# ADC_DSP.net
KiCad netlist of a schematic drawn in EAGLE
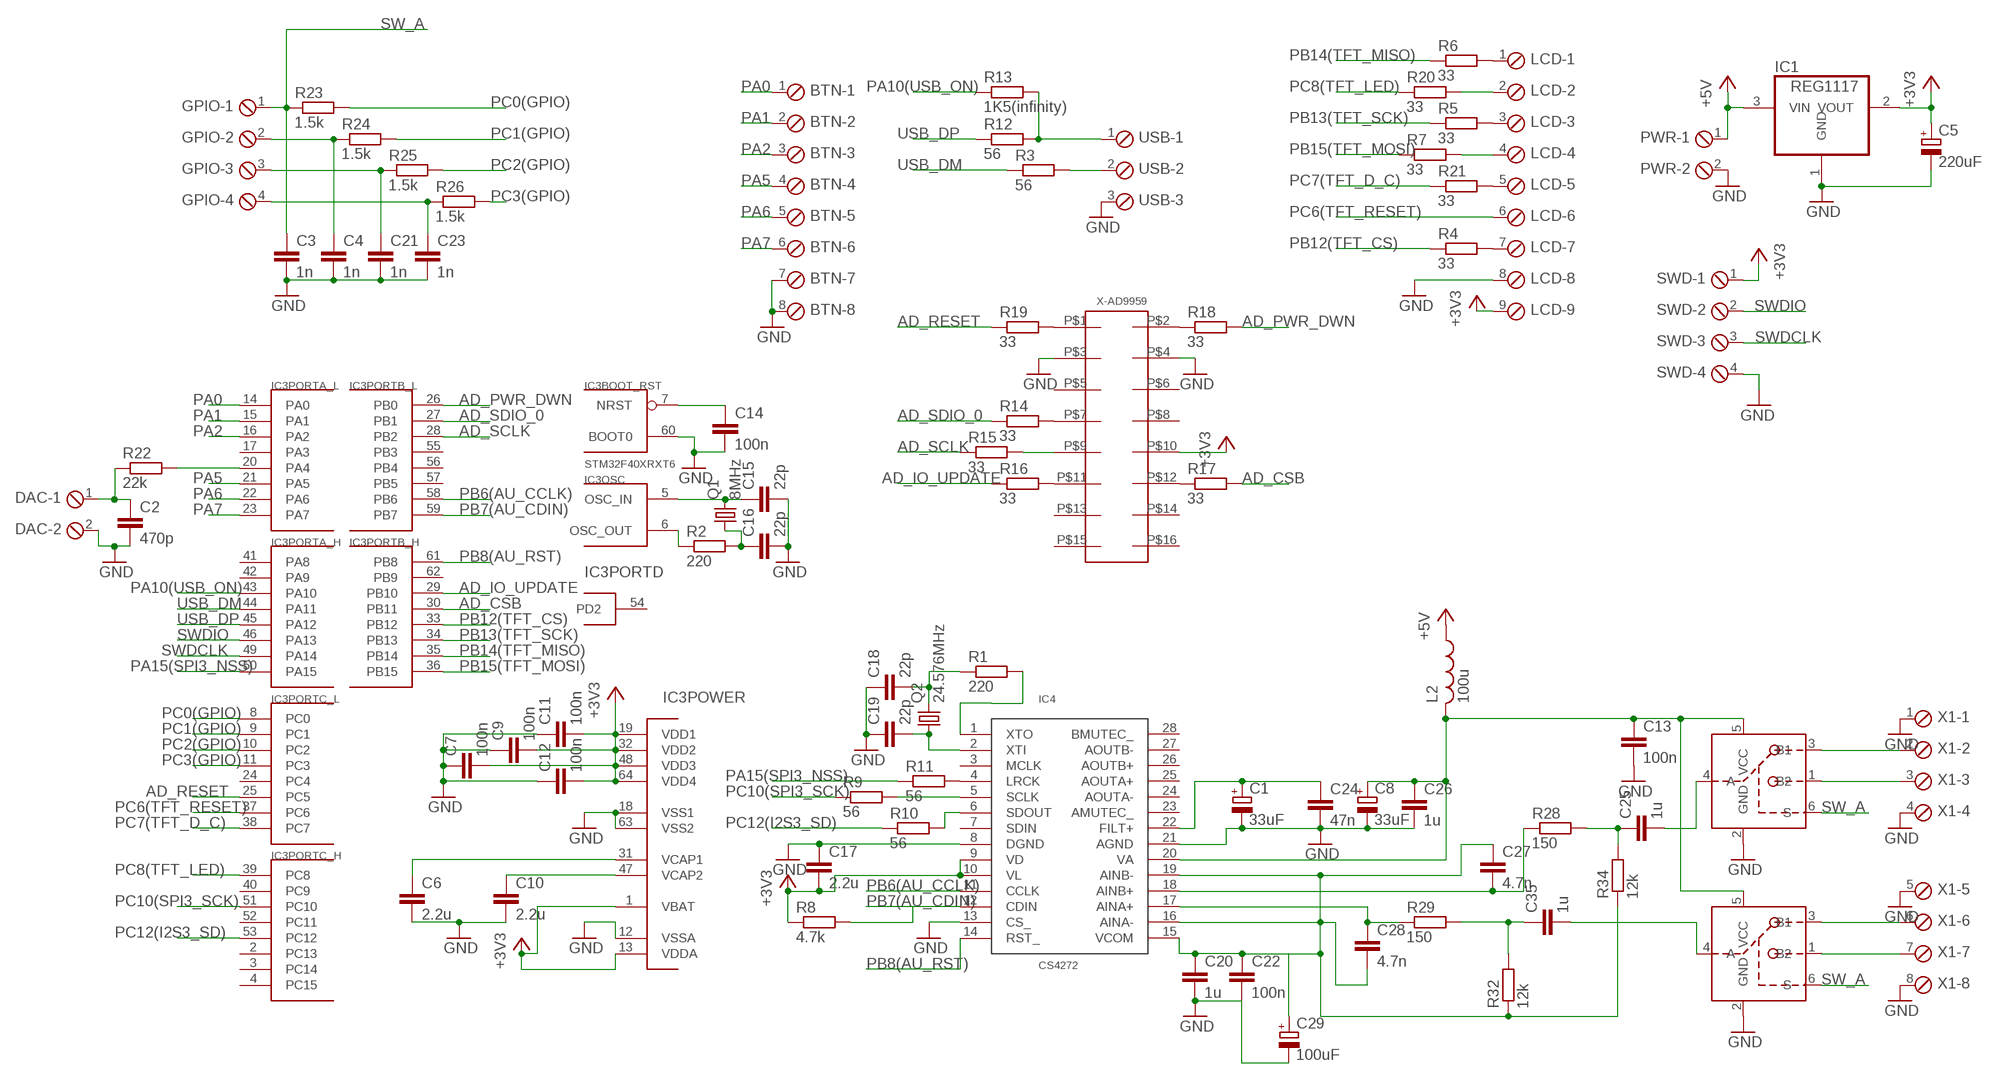
[diagram p0: schematic, sheet 1]

(export (version "E")
  (design (tool "Eeschema 10.0.6"))
  (components
    (comp (ref "BTN")
      (value "MPT8")
      (footprint "eagle-import:8POL254")
      (libsource (lib "eagle-import") (part "MPT8"))
    )
    (comp (ref "C1")
      (value "33uF")
      (footprint "eagle-import:153CLV-0605")
      (libsource (lib "eagle-import") (part "CPOL-EU153CLV-0605"))
    )
    (comp (ref "C2")
      (value "470p")
      (footprint "eagle-import:C0805")
      (libsource (lib "eagle-import") (part "C-EUC0805"))
    )
    (comp (ref "C3")
      (value "1n")
      (footprint "eagle-import:C0805")
      (libsource (lib "eagle-import") (part "C-EUC0805"))
    )
    (comp (ref "C4")
      (value "1n")
      (footprint "eagle-import:C0805")
      (libsource (lib "eagle-import") (part "C-EUC0805"))
    )
    (comp (ref "C5")
      (value "220uF")
      (footprint "eagle-import:153CLV-0605")
      (libsource (lib "eagle-import") (part "CPOL-EU153CLV-0605"))
    )
    (comp (ref "C6")
      (value "2.2u")
      (footprint "eagle-import:C0603")
      (libsource (lib "eagle-import") (part "C-EUC0603"))
    )
    (comp (ref "C7")
      (value "100n")
      (footprint "eagle-import:C0603")
      (libsource (lib "eagle-import") (part "C-EUC0603"))
    )
    (comp (ref "C8")
      (value "33uF")
      (footprint "eagle-import:153CLV-0605")
      (libsource (lib "eagle-import") (part "CPOL-EU153CLV-0605"))
    )
    (comp (ref "C9")
      (value "100n")
      (footprint "eagle-import:C0603")
      (libsource (lib "eagle-import") (part "C-EUC0603"))
    )
    (comp (ref "C10")
      (value "2.2u")
      (footprint "eagle-import:C0603")
      (libsource (lib "eagle-import") (part "C-EUC0603"))
    )
    (comp (ref "C11")
      (value "100n")
      (footprint "eagle-import:C0603")
      (libsource (lib "eagle-import") (part "C-EUC0603"))
    )
    (comp (ref "C12")
      (value "100n")
      (footprint "eagle-import:C0603")
      (libsource (lib "eagle-import") (part "C-EUC0603"))
    )
    (comp (ref "C13")
      (value "100n")
      (footprint "eagle-import:C0603")
      (libsource (lib "eagle-import") (part "C-EUC0603"))
    )
    (comp (ref "C14")
      (value "100n")
      (footprint "eagle-import:C0603")
      (libsource (lib "eagle-import") (part "C-EUC0603"))
    )
    (comp (ref "C15")
      (value "22p")
      (footprint "eagle-import:C0603")
      (libsource (lib "eagle-import") (part "C-EUC0603"))
    )
    (comp (ref "C16")
      (value "22p")
      (footprint "eagle-import:C0603")
      (libsource (lib "eagle-import") (part "C-EUC0603"))
    )
    (comp (ref "C17")
      (value "2.2u")
      (footprint "eagle-import:C0603")
      (libsource (lib "eagle-import") (part "C-EUC0603"))
    )
    (comp (ref "C18")
      (value "22p")
      (footprint "eagle-import:C0603")
      (libsource (lib "eagle-import") (part "C-EUC0603"))
    )
    (comp (ref "C19")
      (value "22p")
      (footprint "eagle-import:C0603")
      (libsource (lib "eagle-import") (part "C-EUC0603"))
    )
    (comp (ref "C20")
      (value "1u")
      (footprint "eagle-import:C0603")
      (libsource (lib "eagle-import") (part "C-EUC0603"))
    )
    (comp (ref "C21")
      (value "1n")
      (footprint "eagle-import:C0805")
      (libsource (lib "eagle-import") (part "C-EUC0805"))
    )
    (comp (ref "C22")
      (value "100n")
      (footprint "eagle-import:C0603")
      (libsource (lib "eagle-import") (part "C-EUC0603"))
    )
    (comp (ref "C23")
      (value "1n")
      (footprint "eagle-import:C0805")
      (libsource (lib "eagle-import") (part "C-EUC0805"))
    )
    (comp (ref "C24")
      (value "47n")
      (footprint "eagle-import:C0805")
      (libsource (lib "eagle-import") (part "C-EUC0805"))
    )
    (comp (ref "C25")
      (value "1u")
      (footprint "eagle-import:C0603")
      (libsource (lib "eagle-import") (part "C-EUC0603"))
    )
    (comp (ref "C26")
      (value "1u")
      (footprint "eagle-import:C0603")
      (libsource (lib "eagle-import") (part "C-EUC0603"))
    )
    (comp (ref "C27")
      (value "4.7n")
      (footprint "eagle-import:C0805")
      (libsource (lib "eagle-import") (part "C-EUC0805"))
    )
    (comp (ref "C28")
      (value "4.7n")
      (footprint "eagle-import:C0805")
      (libsource (lib "eagle-import") (part "C-EUC0805"))
    )
    (comp (ref "C29")
      (value "100uF")
      (footprint "eagle-import:153CLV-0605")
      (libsource (lib "eagle-import") (part "CPOL-EU153CLV-0605"))
    )
    (comp (ref "C35")
      (value "1u")
      (footprint "eagle-import:C0603")
      (libsource (lib "eagle-import") (part "C-EUC0603"))
    )
    (comp (ref "DAC")
      (value "MPT2")
      (footprint "eagle-import:2POL254")
      (libsource (lib "eagle-import") (part "MPT2"))
    )
    (comp (ref "GPIO")
      (value "MPT4")
      (footprint "eagle-import:4POL254")
      (libsource (lib "eagle-import") (part "MPT4"))
    )
    (comp (ref "IC1")
      (value "REG1117")
      (footprint "eagle-import:SOT223")
      (libsource (lib "eagle-import") (part "REG1117"))
    )
    (comp (ref "IC3")
      (value "STM32F40XRXT6")
      (footprint "eagle-import:TQFP64")
      (libsource (lib "eagle-import") (part "STM32F40XRXT6"))
    )
    (comp (ref "IC4")
      (value "CS4272")
      (footprint "eagle-import:TSSOP28")
      (libsource (lib "eagle-import") (part "CS4272"))
    )
    (comp (ref "L2")
      (value "100u")
      (footprint "eagle-import:0207_12")
      (libsource (lib "eagle-import") (part "L-US0207/12"))
    )
    (comp (ref "LCD")
      (value "MPT9")
      (footprint "eagle-import:9POL254")
      (libsource (lib "eagle-import") (part "MPT9"))
    )
    (comp (ref "PWR")
      (value "MPT2")
      (footprint "eagle-import:2POL254")
      (libsource (lib "eagle-import") (part "MPT2"))
    )
    (comp (ref "Q1")
      (value "8MHz")
      (footprint "eagle-import:HC49_S")
      (libsource (lib "eagle-import") (part "CRYSTALHC49S"))
    )
    (comp (ref "Q2")
      (value "24.576MHz")
      (footprint "eagle-import:HC49_S")
      (libsource (lib "eagle-import") (part "CRYSTALHC49S"))
    )
    (comp (ref "R1")
      (value "220")
      (footprint "eagle-import:R0603")
      (libsource (lib "eagle-import") (part "R-EU_R0603"))
    )
    (comp (ref "R2")
      (value "220")
      (footprint "eagle-import:R0603")
      (libsource (lib "eagle-import") (part "R-EU_R0603"))
    )
    (comp (ref "R3")
      (value "56")
      (footprint "eagle-import:R0603")
      (libsource (lib "eagle-import") (part "R-EU_R0603"))
    )
    (comp (ref "R4")
      (value "33")
      (footprint "eagle-import:R0603")
      (libsource (lib "eagle-import") (part "R-EU_R0603"))
    )
    (comp (ref "R5")
      (value "33")
      (footprint "eagle-import:R0603")
      (libsource (lib "eagle-import") (part "R-EU_R0603"))
    )
    (comp (ref "R6")
      (value "33")
      (footprint "eagle-import:R0603")
      (libsource (lib "eagle-import") (part "R-EU_R0603"))
    )
    (comp (ref "R7")
      (value "33")
      (footprint "eagle-import:R0603")
      (libsource (lib "eagle-import") (part "R-EU_R0603"))
    )
    (comp (ref "R8")
      (value "4.7k")
      (footprint "eagle-import:R0603")
      (libsource (lib "eagle-import") (part "R-EU_R0603"))
    )
    (comp (ref "R9")
      (value "56")
      (footprint "eagle-import:R0603")
      (libsource (lib "eagle-import") (part "R-EU_R0603"))
    )
    (comp (ref "R10")
      (value "56")
      (footprint "eagle-import:R0603")
      (libsource (lib "eagle-import") (part "R-EU_R0603"))
    )
    (comp (ref "R11")
      (value "56")
      (footprint "eagle-import:R0603")
      (libsource (lib "eagle-import") (part "R-EU_R0603"))
    )
    (comp (ref "R12")
      (value "56")
      (footprint "eagle-import:R0603")
      (libsource (lib "eagle-import") (part "R-EU_R0603"))
    )
    (comp (ref "R13")
      (value "1K5(infinity)")
      (footprint "eagle-import:R0603")
      (libsource (lib "eagle-import") (part "R-EU_R0603"))
    )
    (comp (ref "R14")
      (value "33")
      (footprint "eagle-import:R0603")
      (libsource (lib "eagle-import") (part "R-EU_R0603"))
    )
    (comp (ref "R15")
      (value "33")
      (footprint "eagle-import:R0603")
      (libsource (lib "eagle-import") (part "R-EU_R0603"))
    )
    (comp (ref "R16")
      (value "33")
      (footprint "eagle-import:R0603")
      (libsource (lib "eagle-import") (part "R-EU_R0603"))
    )
    (comp (ref "R17")
      (value "33")
      (footprint "eagle-import:R0603")
      (libsource (lib "eagle-import") (part "R-EU_R0603"))
    )
    (comp (ref "R18")
      (value "33")
      (footprint "eagle-import:R0603")
      (libsource (lib "eagle-import") (part "R-EU_R0603"))
    )
    (comp (ref "R19")
      (value "33")
      (footprint "eagle-import:R0603")
      (libsource (lib "eagle-import") (part "R-EU_R0603"))
    )
    (comp (ref "R20")
      (value "33")
      (footprint "eagle-import:R0603")
      (libsource (lib "eagle-import") (part "R-EU_R0603"))
    )
    (comp (ref "R21")
      (value "33")
      (footprint "eagle-import:R0603")
      (libsource (lib "eagle-import") (part "R-EU_R0603"))
    )
    (comp (ref "R22")
      (value "22k")
      (footprint "eagle-import:R0603")
      (libsource (lib "eagle-import") (part "R-EU_R0603"))
    )
    (comp (ref "R23")
      (value "1.5k")
      (footprint "eagle-import:R0603")
      (libsource (lib "eagle-import") (part "R-EU_R0603"))
    )
    (comp (ref "R24")
      (value "1.5k")
      (footprint "eagle-import:R0603")
      (libsource (lib "eagle-import") (part "R-EU_R0603"))
    )
    (comp (ref "R25")
      (value "1.5k")
      (footprint "eagle-import:R0603")
      (libsource (lib "eagle-import") (part "R-EU_R0603"))
    )
    (comp (ref "R26")
      (value "1.5k")
      (footprint "eagle-import:R0603")
      (libsource (lib "eagle-import") (part "R-EU_R0603"))
    )
    (comp (ref "R28")
      (value "150")
      (footprint "eagle-import:R0603")
      (libsource (lib "eagle-import") (part "R-EU_R0603"))
    )
    (comp (ref "R29")
      (value "150")
      (footprint "eagle-import:R0603")
      (libsource (lib "eagle-import") (part "R-EU_R0603"))
    )
    (comp (ref "R32")
      (value "12k")
      (footprint "eagle-import:R0603")
      (libsource (lib "eagle-import") (part "R-EU_R0603"))
    )
    (comp (ref "R34")
      (value "12k")
      (footprint "eagle-import:R0603")
      (libsource (lib "eagle-import") (part "R-EU_R0603"))
    )
    (comp (ref "SWD")
      (value "MPT4")
      (footprint "eagle-import:4POL254")
      (libsource (lib "eagle-import") (part "MPT4"))
    )
    (comp (ref "U$1")
      (value "SN74LVC1G3157DBVR")
      (footprint "eagle-import:SOT23-6")
      (libsource (lib "eagle-import") (part "SN74LVC1G3157DBVR"))
    )
    (comp (ref "U$2")
      (value "SN74LVC1G3157DBVR")
      (footprint "eagle-import:SOT23-6")
      (libsource (lib "eagle-import") (part "SN74LVC1G3157DBVR"))
    )
    (comp (ref "USB")
      (value "MPT3")
      (footprint "eagle-import:3POL254")
      (libsource (lib "eagle-import") (part "MPT3"))
    )
    (comp (ref "X-AD9959")
      (value "PIN8X2")
      (footprint "eagle-import:PIN8X2_SMD")
      (libsource (lib "eagle-import") (part "PIN8X2"))
    )
    (comp (ref "X1")
      (value "MPT8")
      (footprint "eagle-import:8POL254")
      (libsource (lib "eagle-import") (part "MPT8"))
    )
  )
  (nets
    (net (code "1") (name "+3V3") (class "Default")
      (node (ref "C11") (pin "2") (pinfunction "2_2") (pintype "passive"))
      (node (ref "C12") (pin "2") (pinfunction "2_2") (pintype "passive"))
      (node (ref "C17") (pin "2") (pinfunction "2_2") (pintype "passive"))
      (node (ref "C5") (pin "+") (pinfunction "+_+") (pintype "passive"))
      (node (ref "C7") (pin "2") (pinfunction "2_2") (pintype "passive"))
      (node (ref "C9") (pin "2") (pinfunction "2_2") (pintype "passive"))
      (node (ref "IC1") (pin "2") (pinfunction "VOUT_2") (pintype "output"))
      (node (ref "IC3") (pin "1") (pinfunction "VBAT_1") (pintype "bidirectional"))
      (node (ref "IC3") (pin "13") (pinfunction "VDDA_13") (pintype "bidirectional"))
      (node (ref "IC3") (pin "19") (pinfunction "VDD1_19") (pintype "bidirectional"))
      (node (ref "IC3") (pin "32") (pinfunction "VDD2_32") (pintype "bidirectional"))
      (node (ref "IC3") (pin "48") (pinfunction "VDD3_48") (pintype "bidirectional"))
      (node (ref "IC3") (pin "64") (pinfunction "VDD4_64") (pintype "bidirectional"))
      (node (ref "IC4") (pin "10") (pinfunction "VL_10") (pintype "bidirectional"))
      (node (ref "IC4") (pin "9") (pinfunction "VD_9") (pintype "bidirectional"))
      (node (ref "LCD") (pin "9") (pinfunction "1_9") (pintype "passive"))
      (node (ref "R8") (pin "1") (pinfunction "1_1") (pintype "passive"))
      (node (ref "SWD") (pin "1") (pinfunction "1_1") (pintype "passive"))
      (node (ref "X-AD9959") (pin "P$10") (pinfunction "P$10_P$10") (pintype "bidirectional"))
    )
    (net (code "2") (name "+5V") (class "Default")
      (node (ref "IC1") (pin "3") (pinfunction "VIN_3") (pintype "input"))
      (node (ref "L2") (pin "1") (pinfunction "1_1") (pintype "passive"))
      (node (ref "PWR") (pin "1") (pinfunction "1_1") (pintype "passive"))
    )
    (net (code "3") (name "/AD_CSB") (class "Default")
      (node (ref "IC3") (pin "30") (pinfunction "PB11_30") (pintype "bidirectional"))
      (node (ref "R17") (pin "2") (pinfunction "2_2") (pintype "passive"))
    )
    (net (code "4") (name "/AD_IO_UPDATE") (class "Default")
      (node (ref "IC3") (pin "29") (pinfunction "PB10_29") (pintype "bidirectional"))
      (node (ref "R16") (pin "1") (pinfunction "1_1") (pintype "passive"))
    )
    (net (code "5") (name "/AD_PWR_DWN") (class "Default")
      (node (ref "IC3") (pin "26") (pinfunction "PB0_26") (pintype "bidirectional"))
      (node (ref "R18") (pin "2") (pinfunction "2_2") (pintype "passive"))
    )
    (net (code "6") (name "/AD_RESET") (class "Default")
      (node (ref "IC3") (pin "25") (pinfunction "PC5_25") (pintype "bidirectional"))
      (node (ref "R19") (pin "1") (pinfunction "1_1") (pintype "passive"))
    )
    (net (code "7") (name "/AD_SCLK") (class "Default")
      (node (ref "IC3") (pin "28") (pinfunction "PB2_28") (pintype "bidirectional"))
      (node (ref "R15") (pin "1") (pinfunction "1_1") (pintype "passive"))
    )
    (net (code "8") (name "/AD_SDIO_0") (class "Default")
      (node (ref "IC3") (pin "27") (pinfunction "PB1_27") (pintype "bidirectional"))
      (node (ref "R14") (pin "1") (pinfunction "1_1") (pintype "passive"))
    )
    (net (code "9") (name "/PA0") (class "Default")
      (node (ref "BTN") (pin "1") (pinfunction "1_1") (pintype "passive"))
      (node (ref "IC3") (pin "14") (pinfunction "PA0_14") (pintype "bidirectional"))
    )
    (net (code "10") (name "/PA1") (class "Default")
      (node (ref "BTN") (pin "2") (pinfunction "1_2") (pintype "passive"))
      (node (ref "IC3") (pin "15") (pinfunction "PA1_15") (pintype "bidirectional"))
    )
    (net (code "11") (name "/PA2") (class "Default")
      (node (ref "BTN") (pin "3") (pinfunction "1_3") (pintype "passive"))
      (node (ref "IC3") (pin "16") (pinfunction "PA2_16") (pintype "bidirectional"))
    )
    (net (code "12") (name "/PA5") (class "Default")
      (node (ref "BTN") (pin "4") (pinfunction "1_4") (pintype "passive"))
      (node (ref "IC3") (pin "21") (pinfunction "PA5_21") (pintype "bidirectional"))
    )
    (net (code "13") (name "/PA6") (class "Default")
      (node (ref "BTN") (pin "5") (pinfunction "1_5") (pintype "passive"))
      (node (ref "IC3") (pin "22") (pinfunction "PA6_22") (pintype "bidirectional"))
    )
    (net (code "14") (name "/PA7") (class "Default")
      (node (ref "BTN") (pin "6") (pinfunction "1_6") (pintype "passive"))
      (node (ref "IC3") (pin "23") (pinfunction "PA7_23") (pintype "bidirectional"))
    )
    (net (code "15") (name "/PA10(USB_ON)") (class "Default")
      (node (ref "IC3") (pin "43") (pinfunction "PA10_43") (pintype "bidirectional"))
      (node (ref "R13") (pin "1") (pinfunction "1_1") (pintype "passive"))
    )
    (net (code "16") (name "/PA15(SPI3_NSS)") (class "Default")
      (node (ref "IC3") (pin "50") (pinfunction "PA15_50") (pintype "bidirectional"))
      (node (ref "R11") (pin "1") (pinfunction "1_1") (pintype "passive"))
    )
    (net (code "17") (name "/PB6(AU_CCLK)") (class "Default")
      (node (ref "IC3") (pin "58") (pinfunction "PB6_58") (pintype "bidirectional"))
      (node (ref "IC4") (pin "11") (pinfunction "CCLK_11") (pintype "bidirectional"))
    )
    (net (code "18") (name "/PB7(AU_CDIN)") (class "Default")
      (node (ref "IC3") (pin "59") (pinfunction "PB7_59") (pintype "bidirectional"))
      (node (ref "IC4") (pin "12") (pinfunction "CDIN_12") (pintype "bidirectional"))
      (node (ref "R8") (pin "2") (pinfunction "2_2") (pintype "passive"))
    )
    (net (code "19") (name "/PB8(AU_RST)") (class "Default")
      (node (ref "IC3") (pin "61") (pinfunction "PB8_61") (pintype "bidirectional"))
      (node (ref "IC4") (pin "14") (pinfunction "RST__14") (pintype "bidirectional"))
    )
    (net (code "20") (name "/PB12(TFT_CS)") (class "Default")
      (node (ref "IC3") (pin "33") (pinfunction "PB12_33") (pintype "bidirectional"))
      (node (ref "R4") (pin "1") (pinfunction "1_1") (pintype "passive"))
    )
    (net (code "21") (name "/PB13(TFT_SCK)") (class "Default")
      (node (ref "IC3") (pin "34") (pinfunction "PB13_34") (pintype "bidirectional"))
      (node (ref "R5") (pin "1") (pinfunction "1_1") (pintype "passive"))
    )
    (net (code "22") (name "/PB14(TFT_MISO)") (class "Default")
      (node (ref "IC3") (pin "35") (pinfunction "PB14_35") (pintype "bidirectional"))
      (node (ref "R6") (pin "1") (pinfunction "1_1") (pintype "passive"))
    )
    (net (code "23") (name "/PB15(TFT_MOSI)") (class "Default")
      (node (ref "IC3") (pin "36") (pinfunction "PB15_36") (pintype "bidirectional"))
      (node (ref "R7") (pin "1") (pinfunction "1_1") (pintype "passive"))
    )
    (net (code "24") (name "/PC0(GPIO)") (class "Default")
      (node (ref "IC3") (pin "8") (pinfunction "PC0_8") (pintype "bidirectional"))
      (node (ref "R23") (pin "2") (pinfunction "2_2") (pintype "passive"))
    )
    (net (code "25") (name "/PC1(GPIO)") (class "Default")
      (node (ref "IC3") (pin "9") (pinfunction "PC1_9") (pintype "bidirectional"))
      (node (ref "R24") (pin "2") (pinfunction "2_2") (pintype "passive"))
    )
    (net (code "26") (name "/PC2(GPIO)") (class "Default")
      (node (ref "IC3") (pin "10") (pinfunction "PC2_10") (pintype "bidirectional"))
      (node (ref "R25") (pin "2") (pinfunction "2_2") (pintype "passive"))
    )
    (net (code "27") (name "/PC3(GPIO)") (class "Default")
      (node (ref "IC3") (pin "11") (pinfunction "PC3_11") (pintype "bidirectional"))
      (node (ref "R26") (pin "2") (pinfunction "2_2") (pintype "passive"))
    )
    (net (code "28") (name "/PC6(TFT_RESET)") (class "Default")
      (node (ref "IC3") (pin "37") (pinfunction "PC6_37") (pintype "bidirectional"))
      (node (ref "LCD") (pin "6") (pinfunction "1_6") (pintype "passive"))
    )
    (net (code "29") (name "/PC7(TFT_D_C)") (class "Default")
      (node (ref "IC3") (pin "38") (pinfunction "PC7_38") (pintype "bidirectional"))
      (node (ref "R21") (pin "1") (pinfunction "1_1") (pintype "passive"))
    )
    (net (code "30") (name "/PC8(TFT_LED)") (class "Default")
      (node (ref "IC3") (pin "39") (pinfunction "PC8_39") (pintype "bidirectional"))
      (node (ref "R20") (pin "1") (pinfunction "1_1") (pintype "passive"))
    )
    (net (code "31") (name "/PC10(SPI3_SCK)") (class "Default")
      (node (ref "IC3") (pin "51") (pinfunction "PC10_51") (pintype "bidirectional"))
      (node (ref "R9") (pin "1") (pinfunction "1_1") (pintype "passive"))
    )
    (net (code "32") (name "/PC12(I2S3_SD)") (class "Default")
      (node (ref "IC3") (pin "53") (pinfunction "PC12_53") (pintype "bidirectional"))
      (node (ref "R10") (pin "1") (pinfunction "1_1") (pintype "passive"))
    )
    (net (code "33") (name "/SWDCLK") (class "Default")
      (node (ref "IC3") (pin "49") (pinfunction "PA14_49") (pintype "bidirectional"))
      (node (ref "SWD") (pin "3") (pinfunction "1_3") (pintype "passive"))
    )
    (net (code "34") (name "/SWDIO") (class "Default")
      (node (ref "IC3") (pin "46") (pinfunction "PA13_46") (pintype "bidirectional"))
      (node (ref "SWD") (pin "2") (pinfunction "1_2") (pintype "passive"))
    )
    (net (code "35") (name "/SW_A") (class "Default")
      (node (ref "C3") (pin "1") (pinfunction "1_1") (pintype "passive"))
      (node (ref "GPIO") (pin "1") (pinfunction "1_1") (pintype "passive"))
      (node (ref "R23") (pin "1") (pinfunction "1_1") (pintype "passive"))
      (node (ref "U$1") (pin "6") (pinfunction "S_6") (pintype "bidirectional"))
      (node (ref "U$2") (pin "6") (pinfunction "S_6") (pintype "bidirectional"))
    )
    (net (code "36") (name "/USB_DM") (class "Default")
      (node (ref "IC3") (pin "44") (pinfunction "PA11_44") (pintype "bidirectional"))
      (node (ref "R3") (pin "1") (pinfunction "1_1") (pintype "passive"))
    )
    (net (code "37") (name "/USB_DP") (class "Default")
      (node (ref "IC3") (pin "45") (pinfunction "PA12_45") (pintype "bidirectional"))
      (node (ref "R12") (pin "1") (pinfunction "1_1") (pintype "passive"))
    )
    (net (code "38") (name "GND") (class "Default")
      (node (ref "BTN") (pin "7") (pinfunction "1_7") (pintype "passive"))
      (node (ref "BTN") (pin "8") (pinfunction "1_8") (pintype "passive"))
      (node (ref "C1") (pin "-") (pinfunction "-_-") (pintype "passive"))
      (node (ref "C10") (pin "2") (pinfunction "2_2") (pintype "passive"))
      (node (ref "C11") (pin "1") (pinfunction "1_1") (pintype "passive"))
      (node (ref "C12") (pin "1") (pinfunction "1_1") (pintype "passive"))
      (node (ref "C13") (pin "2") (pinfunction "2_2") (pintype "passive"))
      (node (ref "C14") (pin "2") (pinfunction "2_2") (pintype "passive"))
      (node (ref "C15") (pin "2") (pinfunction "2_2") (pintype "passive"))
      (node (ref "C16") (pin "2") (pinfunction "2_2") (pintype "passive"))
      (node (ref "C17") (pin "1") (pinfunction "1_1") (pintype "passive"))
      (node (ref "C18") (pin "1") (pinfunction "1_1") (pintype "passive"))
      (node (ref "C19") (pin "1") (pinfunction "1_1") (pintype "passive"))
      (node (ref "C2") (pin "2") (pinfunction "2_2") (pintype "passive"))
      (node (ref "C20") (pin "2") (pinfunction "2_2") (pintype "passive"))
      (node (ref "C21") (pin "2") (pinfunction "2_2") (pintype "passive"))
      (node (ref "C22") (pin "2") (pinfunction "2_2") (pintype "passive"))
      (node (ref "C23") (pin "2") (pinfunction "2_2") (pintype "passive"))
      (node (ref "C24") (pin "2") (pinfunction "2_2") (pintype "passive"))
      (node (ref "C26") (pin "2") (pinfunction "2_2") (pintype "passive"))
      (node (ref "C29") (pin "-") (pinfunction "-_-") (pintype "passive"))
      (node (ref "C3") (pin "2") (pinfunction "2_2") (pintype "passive"))
      (node (ref "C4") (pin "2") (pinfunction "2_2") (pintype "passive"))
      (node (ref "C5") (pin "-") (pinfunction "-_-") (pintype "passive"))
      (node (ref "C6") (pin "2") (pinfunction "2_2") (pintype "passive"))
      (node (ref "C7") (pin "1") (pinfunction "1_1") (pintype "passive"))
      (node (ref "C8") (pin "-") (pinfunction "-_-") (pintype "passive"))
      (node (ref "C9") (pin "1") (pinfunction "1_1") (pintype "passive"))
      (node (ref "DAC") (pin "2") (pinfunction "1_2") (pintype "passive"))
      (node (ref "IC1") (pin "1") (pinfunction "GND_1") (pintype "power_in"))
      (node (ref "IC3") (pin "12") (pinfunction "VSSA_12") (pintype "bidirectional"))
      (node (ref "IC3") (pin "18") (pinfunction "VSS1_18") (pintype "bidirectional"))
      (node (ref "IC3") (pin "60") (pinfunction "BOOT0_60") (pintype "input"))
      (node (ref "IC3") (pin "63") (pinfunction "VSS2_63") (pintype "bidirectional"))
      (node (ref "IC4") (pin "13") (pinfunction "CS__13") (pintype "bidirectional"))
      (node (ref "IC4") (pin "21") (pinfunction "AGND_21") (pintype "bidirectional"))
      (node (ref "IC4") (pin "8") (pinfunction "DGND_8") (pintype "bidirectional"))
      (node (ref "LCD") (pin "8") (pinfunction "1_8") (pintype "passive"))
      (node (ref "PWR") (pin "2") (pinfunction "1_2") (pintype "passive"))
      (node (ref "SWD") (pin "4") (pinfunction "1_4") (pintype "passive"))
      (node (ref "U$1") (pin "2") (pinfunction "GND_2") (pintype "power_in"))
      (node (ref "U$2") (pin "2") (pinfunction "GND_2") (pintype "power_in"))
      (node (ref "USB") (pin "3") (pinfunction "1_3") (pintype "passive"))
      (node (ref "X-AD9959") (pin "P$3") (pinfunction "P$3_P$3") (pintype "bidirectional"))
      (node (ref "X-AD9959") (pin "P$4") (pinfunction "P$4_P$4") (pintype "bidirectional"))
      (node (ref "X1") (pin "1") (pinfunction "1_1") (pintype "passive"))
      (node (ref "X1") (pin "4") (pinfunction "1_4") (pintype "passive"))
      (node (ref "X1") (pin "5") (pinfunction "1_5") (pintype "passive"))
      (node (ref "X1") (pin "8") (pinfunction "1_8") (pintype "passive"))
    )
    (net (code "39") (name "Net-(C2-Pad1)") (class "Default")
      (node (ref "C2") (pin "1") (pinfunction "1_1") (pintype "passive"))
      (node (ref "DAC") (pin "1") (pinfunction "1_1") (pintype "passive"))
      (node (ref "R22") (pin "1") (pinfunction "1_1") (pintype "passive"))
    )
    (net (code "40") (name "Net-(C16-Pad1)") (class "Default")
      (node (ref "C16") (pin "1") (pinfunction "1_1") (pintype "passive"))
      (node (ref "Q1") (pin "1") (pinfunction "1_1") (pintype "passive"))
      (node (ref "R2") (pin "2") (pinfunction "2_2") (pintype "passive"))
    )
    (net (code "41") (name "Net-(C18-Pad2)") (class "Default")
      (node (ref "C18") (pin "2") (pinfunction "2_2") (pintype "passive"))
      (node (ref "Q2") (pin "2") (pinfunction "2_2") (pintype "passive"))
      (node (ref "R1") (pin "1") (pinfunction "1_1") (pintype "passive"))
    )
    (net (code "42") (name "Net-(C25-Pad1)") (class "Default")
      (node (ref "C25") (pin "1") (pinfunction "1_1") (pintype "passive"))
      (node (ref "R28") (pin "2") (pinfunction "2_2") (pintype "passive"))
      (node (ref "R34") (pin "2") (pinfunction "2_2") (pintype "passive"))
    )
    (net (code "43") (name "Net-(C35-Pad1)") (class "Default")
      (node (ref "C35") (pin "1") (pinfunction "1_1") (pintype "passive"))
      (node (ref "R29") (pin "2") (pinfunction "2_2") (pintype "passive"))
      (node (ref "R32") (pin "2") (pinfunction "2_2") (pintype "passive"))
    )
    (net (code "44") (name "Net-(GPIOB-1)") (class "Default")
      (node (ref "C4") (pin "1") (pinfunction "1_1") (pintype "passive"))
      (node (ref "GPIO") (pin "2") (pinfunction "1_2") (pintype "passive"))
      (node (ref "R24") (pin "1") (pinfunction "1_1") (pintype "passive"))
    )
    (net (code "45") (name "Net-(GPIOC-1)") (class "Default")
      (node (ref "C21") (pin "1") (pinfunction "1_1") (pintype "passive"))
      (node (ref "GPIO") (pin "3") (pinfunction "1_3") (pintype "passive"))
      (node (ref "R25") (pin "1") (pinfunction "1_1") (pintype "passive"))
    )
    (net (code "46") (name "Net-(GPIOD-1)") (class "Default")
      (node (ref "C23") (pin "1") (pinfunction "1_1") (pintype "passive"))
      (node (ref "GPIO") (pin "4") (pinfunction "1_4") (pintype "passive"))
      (node (ref "R26") (pin "1") (pinfunction "1_1") (pintype "passive"))
    )
    (net (code "47") (name "Net-(IC3A-NRST)") (class "Default")
      (node (ref "C14") (pin "1") (pinfunction "1_1") (pintype "passive"))
      (node (ref "IC3") (pin "7") (pinfunction "NRST_7") (pintype "input"))
    )
    (net (code "48") (name "Net-(IC3B-OSC_IN)") (class "Default")
      (node (ref "C15") (pin "1") (pinfunction "1_1") (pintype "passive"))
      (node (ref "IC3") (pin "5") (pinfunction "OSC_IN_5") (pintype "input"))
      (node (ref "Q1") (pin "2") (pinfunction "2_2") (pintype "passive"))
    )
    (net (code "49") (name "Net-(IC3B-OSC_OUT)") (class "Default")
      (node (ref "IC3") (pin "6") (pinfunction "OSC_OUT_6") (pintype "output"))
      (node (ref "R2") (pin "1") (pinfunction "1_1") (pintype "passive"))
    )
    (net (code "50") (name "Net-(IC3D-PA4)") (class "Default")
      (node (ref "IC3") (pin "20") (pinfunction "PA4_20") (pintype "bidirectional"))
      (node (ref "R22") (pin "2") (pinfunction "2_2") (pintype "passive"))
    )
    (net (code "51") (name "Net-(IC3J-VCAP1)") (class "Default")
      (node (ref "C6") (pin "1") (pinfunction "1_1") (pintype "passive"))
      (node (ref "IC3") (pin "31") (pinfunction "VCAP1_31") (pintype "bidirectional"))
    )
    (net (code "52") (name "Net-(IC3J-VCAP2)") (class "Default")
      (node (ref "C10") (pin "1") (pinfunction "1_1") (pintype "passive"))
      (node (ref "IC3") (pin "47") (pinfunction "VCAP2_47") (pintype "bidirectional"))
    )
    (net (code "53") (name "Net-(IC4-AINA+)") (class "Default")
      (node (ref "C28") (pin "1") (pinfunction "1_1") (pintype "passive"))
      (node (ref "IC4") (pin "17") (pinfunction "AINA+_17") (pintype "bidirectional"))
      (node (ref "R29") (pin "1") (pinfunction "1_1") (pintype "passive"))
    )
    (net (code "54") (name "Net-(IC4-AINA-)") (class "Default")
      (node (ref "C20") (pin "1") (pinfunction "1_1") (pintype "passive"))
      (node (ref "C22") (pin "1") (pinfunction "1_1") (pintype "passive"))
      (node (ref "C27") (pin "1") (pinfunction "1_1") (pintype "passive"))
      (node (ref "C28") (pin "2") (pinfunction "2_2") (pintype "passive"))
      (node (ref "C29") (pin "+") (pinfunction "+_+") (pintype "passive"))
      (node (ref "IC4") (pin "15") (pinfunction "VCOM_15") (pintype "bidirectional"))
      (node (ref "IC4") (pin "16") (pinfunction "AINA-_16") (pintype "bidirectional"))
      (node (ref "IC4") (pin "19") (pinfunction "AINB-_19") (pintype "bidirectional"))
      (node (ref "R32") (pin "1") (pinfunction "1_1") (pintype "passive"))
      (node (ref "R34") (pin "1") (pinfunction "1_1") (pintype "passive"))
    )
    (net (code "55") (name "Net-(IC4-AINB+)") (class "Default")
      (node (ref "C27") (pin "2") (pinfunction "2_2") (pintype "passive"))
      (node (ref "IC4") (pin "18") (pinfunction "AINB+_18") (pintype "bidirectional"))
      (node (ref "R28") (pin "1") (pinfunction "1_1") (pintype "passive"))
    )
    (net (code "56") (name "Net-(IC4-FILT+)") (class "Default")
      (node (ref "C1") (pin "+") (pinfunction "+_+") (pintype "passive"))
      (node (ref "C24") (pin "1") (pinfunction "1_1") (pintype "passive"))
      (node (ref "IC4") (pin "22") (pinfunction "FILT+_22") (pintype "bidirectional"))
    )
    (net (code "57") (name "Net-(IC4-LRCK)") (class "Default")
      (node (ref "IC4") (pin "4") (pinfunction "LRCK_4") (pintype "bidirectional"))
      (node (ref "R11") (pin "2") (pinfunction "2_2") (pintype "passive"))
    )
    (net (code "58") (name "Net-(IC4-SCLK)") (class "Default")
      (node (ref "IC4") (pin "5") (pinfunction "SCLK_5") (pintype "bidirectional"))
      (node (ref "R9") (pin "2") (pinfunction "2_2") (pintype "passive"))
    )
    (net (code "59") (name "Net-(IC4-SDOUT)") (class "Default")
      (node (ref "IC4") (pin "6") (pinfunction "SDOUT_6") (pintype "bidirectional"))
      (node (ref "R10") (pin "2") (pinfunction "2_2") (pintype "passive"))
    )
    (net (code "60") (name "Net-(IC4-VA)") (class "Default")
      (node (ref "C13") (pin "1") (pinfunction "1_1") (pintype "passive"))
      (node (ref "C26") (pin "1") (pinfunction "1_1") (pintype "passive"))
      (node (ref "C8") (pin "+") (pinfunction "+_+") (pintype "passive"))
      (node (ref "IC4") (pin "20") (pinfunction "VA_20") (pintype "bidirectional"))
      (node (ref "L2") (pin "2") (pinfunction "2_2") (pintype "passive"))
      (node (ref "U$1") (pin "5") (pinfunction "VCC_5") (pintype "power_in"))
      (node (ref "U$2") (pin "5") (pinfunction "VCC_5") (pintype "power_in"))
    )
    (net (code "61") (name "Net-(IC4-XTI)") (class "Default")
      (node (ref "C19") (pin "2") (pinfunction "2_2") (pintype "passive"))
      (node (ref "IC4") (pin "2") (pinfunction "XTI_2") (pintype "bidirectional"))
      (node (ref "Q2") (pin "1") (pinfunction "1_1") (pintype "passive"))
    )
    (net (code "62") (name "Net-(IC4-XTO)") (class "Default")
      (node (ref "IC4") (pin "1") (pinfunction "XTO_1") (pintype "bidirectional"))
      (node (ref "R1") (pin "2") (pinfunction "2_2") (pintype "passive"))
    )
    (net (code "63") (name "Net-(LCD-Pad1)") (class "Default")
      (node (ref "LCD") (pin "1") (pinfunction "1_1") (pintype "passive"))
      (node (ref "R6") (pin "2") (pinfunction "2_2") (pintype "passive"))
    )
    (net (code "64") (name "Net-(LCDB-1)") (class "Default")
      (node (ref "LCD") (pin "2") (pinfunction "1_2") (pintype "passive"))
      (node (ref "R20") (pin "2") (pinfunction "2_2") (pintype "passive"))
    )
    (net (code "65") (name "Net-(LCDC-1)") (class "Default")
      (node (ref "LCD") (pin "3") (pinfunction "1_3") (pintype "passive"))
      (node (ref "R5") (pin "2") (pinfunction "2_2") (pintype "passive"))
    )
    (net (code "66") (name "Net-(LCDD-1)") (class "Default")
      (node (ref "LCD") (pin "4") (pinfunction "1_4") (pintype "passive"))
      (node (ref "R7") (pin "2") (pinfunction "2_2") (pintype "passive"))
    )
    (net (code "67") (name "Net-(LCDE-1)") (class "Default")
      (node (ref "LCD") (pin "5") (pinfunction "1_5") (pintype "passive"))
      (node (ref "R21") (pin "2") (pinfunction "2_2") (pintype "passive"))
    )
    (net (code "68") (name "Net-(LCDG-1)") (class "Default")
      (node (ref "LCD") (pin "7") (pinfunction "1_7") (pintype "passive"))
      (node (ref "R4") (pin "2") (pinfunction "2_2") (pintype "passive"))
    )
    (net (code "69") (name "Net-(R12-Pad2)") (class "Default")
      (node (ref "R12") (pin "2") (pinfunction "2_2") (pintype "passive"))
      (node (ref "R13") (pin "2") (pinfunction "2_2") (pintype "passive"))
      (node (ref "USB") (pin "1") (pinfunction "1_1") (pintype "passive"))
    )
    (net (code "70") (name "Net-(R14-Pad2)") (class "Default")
      (node (ref "R14") (pin "2") (pinfunction "2_2") (pintype "passive"))
      (node (ref "X-AD9959") (pin "P$7") (pinfunction "P$7_P$7") (pintype "bidirectional"))
    )
    (net (code "71") (name "Net-(R15-Pad2)") (class "Default")
      (node (ref "R15") (pin "2") (pinfunction "2_2") (pintype "passive"))
      (node (ref "X-AD9959") (pin "P$9") (pinfunction "P$9_P$9") (pintype "bidirectional"))
    )
    (net (code "72") (name "Net-(R16-Pad2)") (class "Default")
      (node (ref "R16") (pin "2") (pinfunction "2_2") (pintype "passive"))
      (node (ref "X-AD9959") (pin "P$11") (pinfunction "P$11_P$11") (pintype "bidirectional"))
    )
    (net (code "73") (name "Net-(R17-Pad1)") (class "Default")
      (node (ref "R17") (pin "1") (pinfunction "1_1") (pintype "passive"))
      (node (ref "X-AD9959") (pin "P$12") (pinfunction "P$12_P$12") (pintype "bidirectional"))
    )
    (net (code "74") (name "Net-(R18-Pad1)") (class "Default")
      (node (ref "R18") (pin "1") (pinfunction "1_1") (pintype "passive"))
      (node (ref "X-AD9959") (pin "P$2") (pinfunction "P$2_P$2") (pintype "bidirectional"))
    )
    (net (code "75") (name "Net-(R19-Pad2)") (class "Default")
      (node (ref "R19") (pin "2") (pinfunction "2_2") (pintype "passive"))
      (node (ref "X-AD9959") (pin "P$1") (pinfunction "P$1_P$1") (pintype "bidirectional"))
    )
    (net (code "76") (name "Net-(U$1-A)") (class "Default")
      (node (ref "C25") (pin "2") (pinfunction "2_2") (pintype "passive"))
      (node (ref "U$1") (pin "4") (pinfunction "A_4") (pintype "bidirectional"))
    )
    (net (code "77") (name "Net-(U$1-B1)") (class "Default")
      (node (ref "U$1") (pin "3") (pinfunction "B1_3") (pintype "bidirectional"))
      (node (ref "X1") (pin "2") (pinfunction "1_2") (pintype "passive"))
    )
    (net (code "78") (name "Net-(U$1-B2)") (class "Default")
      (node (ref "U$1") (pin "1") (pinfunction "B2_1") (pintype "bidirectional"))
      (node (ref "X1") (pin "3") (pinfunction "1_3") (pintype "passive"))
    )
    (net (code "79") (name "Net-(U$2-A)") (class "Default")
      (node (ref "C35") (pin "2") (pinfunction "2_2") (pintype "passive"))
      (node (ref "U$2") (pin "4") (pinfunction "A_4") (pintype "bidirectional"))
    )
    (net (code "80") (name "Net-(U$2-B1)") (class "Default")
      (node (ref "U$2") (pin "3") (pinfunction "B1_3") (pintype "bidirectional"))
      (node (ref "X1") (pin "6") (pinfunction "1_6") (pintype "passive"))
    )
    (net (code "81") (name "Net-(U$2-B2)") (class "Default")
      (node (ref "U$2") (pin "1") (pinfunction "B2_1") (pintype "bidirectional"))
      (node (ref "X1") (pin "7") (pinfunction "1_7") (pintype "passive"))
    )
    (net (code "82") (name "Net-(USBB-1)") (class "Default")
      (node (ref "R3") (pin "2") (pinfunction "2_2") (pintype "passive"))
      (node (ref "USB") (pin "2") (pinfunction "1_2") (pintype "passive"))
    )
    (net (code "83") (name "unconnected-(IC3C-PA8-Pad41)") (class "Default")
      (node (ref "IC3") (pin "41") (pinfunction "PA8_41") (pintype "bidirectional"))
    )
    (net (code "84") (name "unconnected-(IC3C-PA9-Pad42)") (class "Default")
      (node (ref "IC3") (pin "42") (pinfunction "PA9_42") (pintype "bidirectional"))
    )
    (net (code "85") (name "unconnected-(IC3D-PA3-Pad17)") (class "Default")
      (node (ref "IC3") (pin "17") (pinfunction "PA3_17") (pintype "bidirectional"))
    )
    (net (code "86") (name "unconnected-(IC3E-PB9-Pad62)") (class "Default")
      (node (ref "IC3") (pin "62") (pinfunction "PB9_62") (pintype "bidirectional"))
    )
    (net (code "87") (name "unconnected-(IC3F-PB3-Pad55)") (class "Default")
      (node (ref "IC3") (pin "55") (pinfunction "PB3_55") (pintype "bidirectional"))
    )
    (net (code "88") (name "unconnected-(IC3F-PB4-Pad56)") (class "Default")
      (node (ref "IC3") (pin "56") (pinfunction "PB4_56") (pintype "bidirectional"))
    )
    (net (code "89") (name "unconnected-(IC3F-PB5-Pad57)") (class "Default")
      (node (ref "IC3") (pin "57") (pinfunction "PB5_57") (pintype "bidirectional"))
    )
    (net (code "90") (name "unconnected-(IC3G-PC9-Pad40)") (class "Default")
      (node (ref "IC3") (pin "40") (pinfunction "PC9_40") (pintype "bidirectional"))
    )
    (net (code "91") (name "unconnected-(IC3G-PC11-Pad52)") (class "Default")
      (node (ref "IC3") (pin "52") (pinfunction "PC11_52") (pintype "bidirectional"))
    )
    (net (code "92") (name "unconnected-(IC3G-PC13-Pad2)") (class "Default")
      (node (ref "IC3") (pin "2") (pinfunction "PC13_2") (pintype "bidirectional"))
    )
    (net (code "93") (name "unconnected-(IC3G-PC14-Pad3)") (class "Default")
      (node (ref "IC3") (pin "3") (pinfunction "PC14_3") (pintype "bidirectional"))
    )
    (net (code "94") (name "unconnected-(IC3G-PC15-Pad4)") (class "Default")
      (node (ref "IC3") (pin "4") (pinfunction "PC15_4") (pintype "bidirectional"))
    )
    (net (code "95") (name "unconnected-(IC3H-PC4-Pad24)") (class "Default")
      (node (ref "IC3") (pin "24") (pinfunction "PC4_24") (pintype "bidirectional"))
    )
    (net (code "96") (name "unconnected-(IC3I-PD2-Pad54)") (class "Default")
      (node (ref "IC3") (pin "54") (pinfunction "PD2_54") (pintype "bidirectional"))
    )
    (net (code "97") (name "unconnected-(IC4-AMUTEC_-Pad23)") (class "Default")
      (node (ref "IC4") (pin "23") (pinfunction "AMUTEC__23") (pintype "bidirectional"))
    )
    (net (code "98") (name "unconnected-(IC4-AOUTA+-Pad25)") (class "Default")
      (node (ref "IC4") (pin "25") (pinfunction "AOUTA+_25") (pintype "bidirectional"))
    )
    (net (code "99") (name "unconnected-(IC4-AOUTA--Pad24)") (class "Default")
      (node (ref "IC4") (pin "24") (pinfunction "AOUTA-_24") (pintype "bidirectional"))
    )
    (net (code "100") (name "unconnected-(IC4-AOUTB+-Pad26)") (class "Default")
      (node (ref "IC4") (pin "26") (pinfunction "AOUTB+_26") (pintype "bidirectional"))
    )
    (net (code "101") (name "unconnected-(IC4-AOUTB--Pad27)") (class "Default")
      (node (ref "IC4") (pin "27") (pinfunction "AOUTB-_27") (pintype "bidirectional"))
    )
    (net (code "102") (name "unconnected-(IC4-BMUTEC_-Pad28)") (class "Default")
      (node (ref "IC4") (pin "28") (pinfunction "BMUTEC__28") (pintype "bidirectional"))
    )
    (net (code "103") (name "unconnected-(IC4-MCLK-Pad3)") (class "Default")
      (node (ref "IC4") (pin "3") (pinfunction "MCLK_3") (pintype "bidirectional"))
    )
    (net (code "104") (name "unconnected-(IC4-SDIN-Pad7)") (class "Default")
      (node (ref "IC4") (pin "7") (pinfunction "SDIN_7") (pintype "bidirectional"))
    )
    (net (code "105") (name "unconnected-(X-AD9959-PadP$5)") (class "Default")
      (node (ref "X-AD9959") (pin "P$5") (pinfunction "P$5_P$5") (pintype "bidirectional"))
    )
    (net (code "106") (name "unconnected-(X-AD9959-PadP$6)") (class "Default")
      (node (ref "X-AD9959") (pin "P$6") (pinfunction "P$6_P$6") (pintype "bidirectional"))
    )
    (net (code "107") (name "unconnected-(X-AD9959-PadP$8)") (class "Default")
      (node (ref "X-AD9959") (pin "P$8") (pinfunction "P$8_P$8") (pintype "bidirectional"))
    )
    (net (code "108") (name "unconnected-(X-AD9959-PadP$13)") (class "Default")
      (node (ref "X-AD9959") (pin "P$13") (pinfunction "P$13_P$13") (pintype "bidirectional"))
    )
    (net (code "109") (name "unconnected-(X-AD9959-PadP$14)") (class "Default")
      (node (ref "X-AD9959") (pin "P$14") (pinfunction "P$14_P$14") (pintype "bidirectional"))
    )
    (net (code "110") (name "unconnected-(X-AD9959-PadP$15)") (class "Default")
      (node (ref "X-AD9959") (pin "P$15") (pinfunction "P$15_P$15") (pintype "bidirectional"))
    )
    (net (code "111") (name "unconnected-(X-AD9959-PadP$16)") (class "Default")
      (node (ref "X-AD9959") (pin "P$16") (pinfunction "P$16_P$16") (pintype "bidirectional"))
    )
  )
)
